# SCH_ch559_2022-01-07.net
KiCad netlist of a schematic drawn in EasyEDA
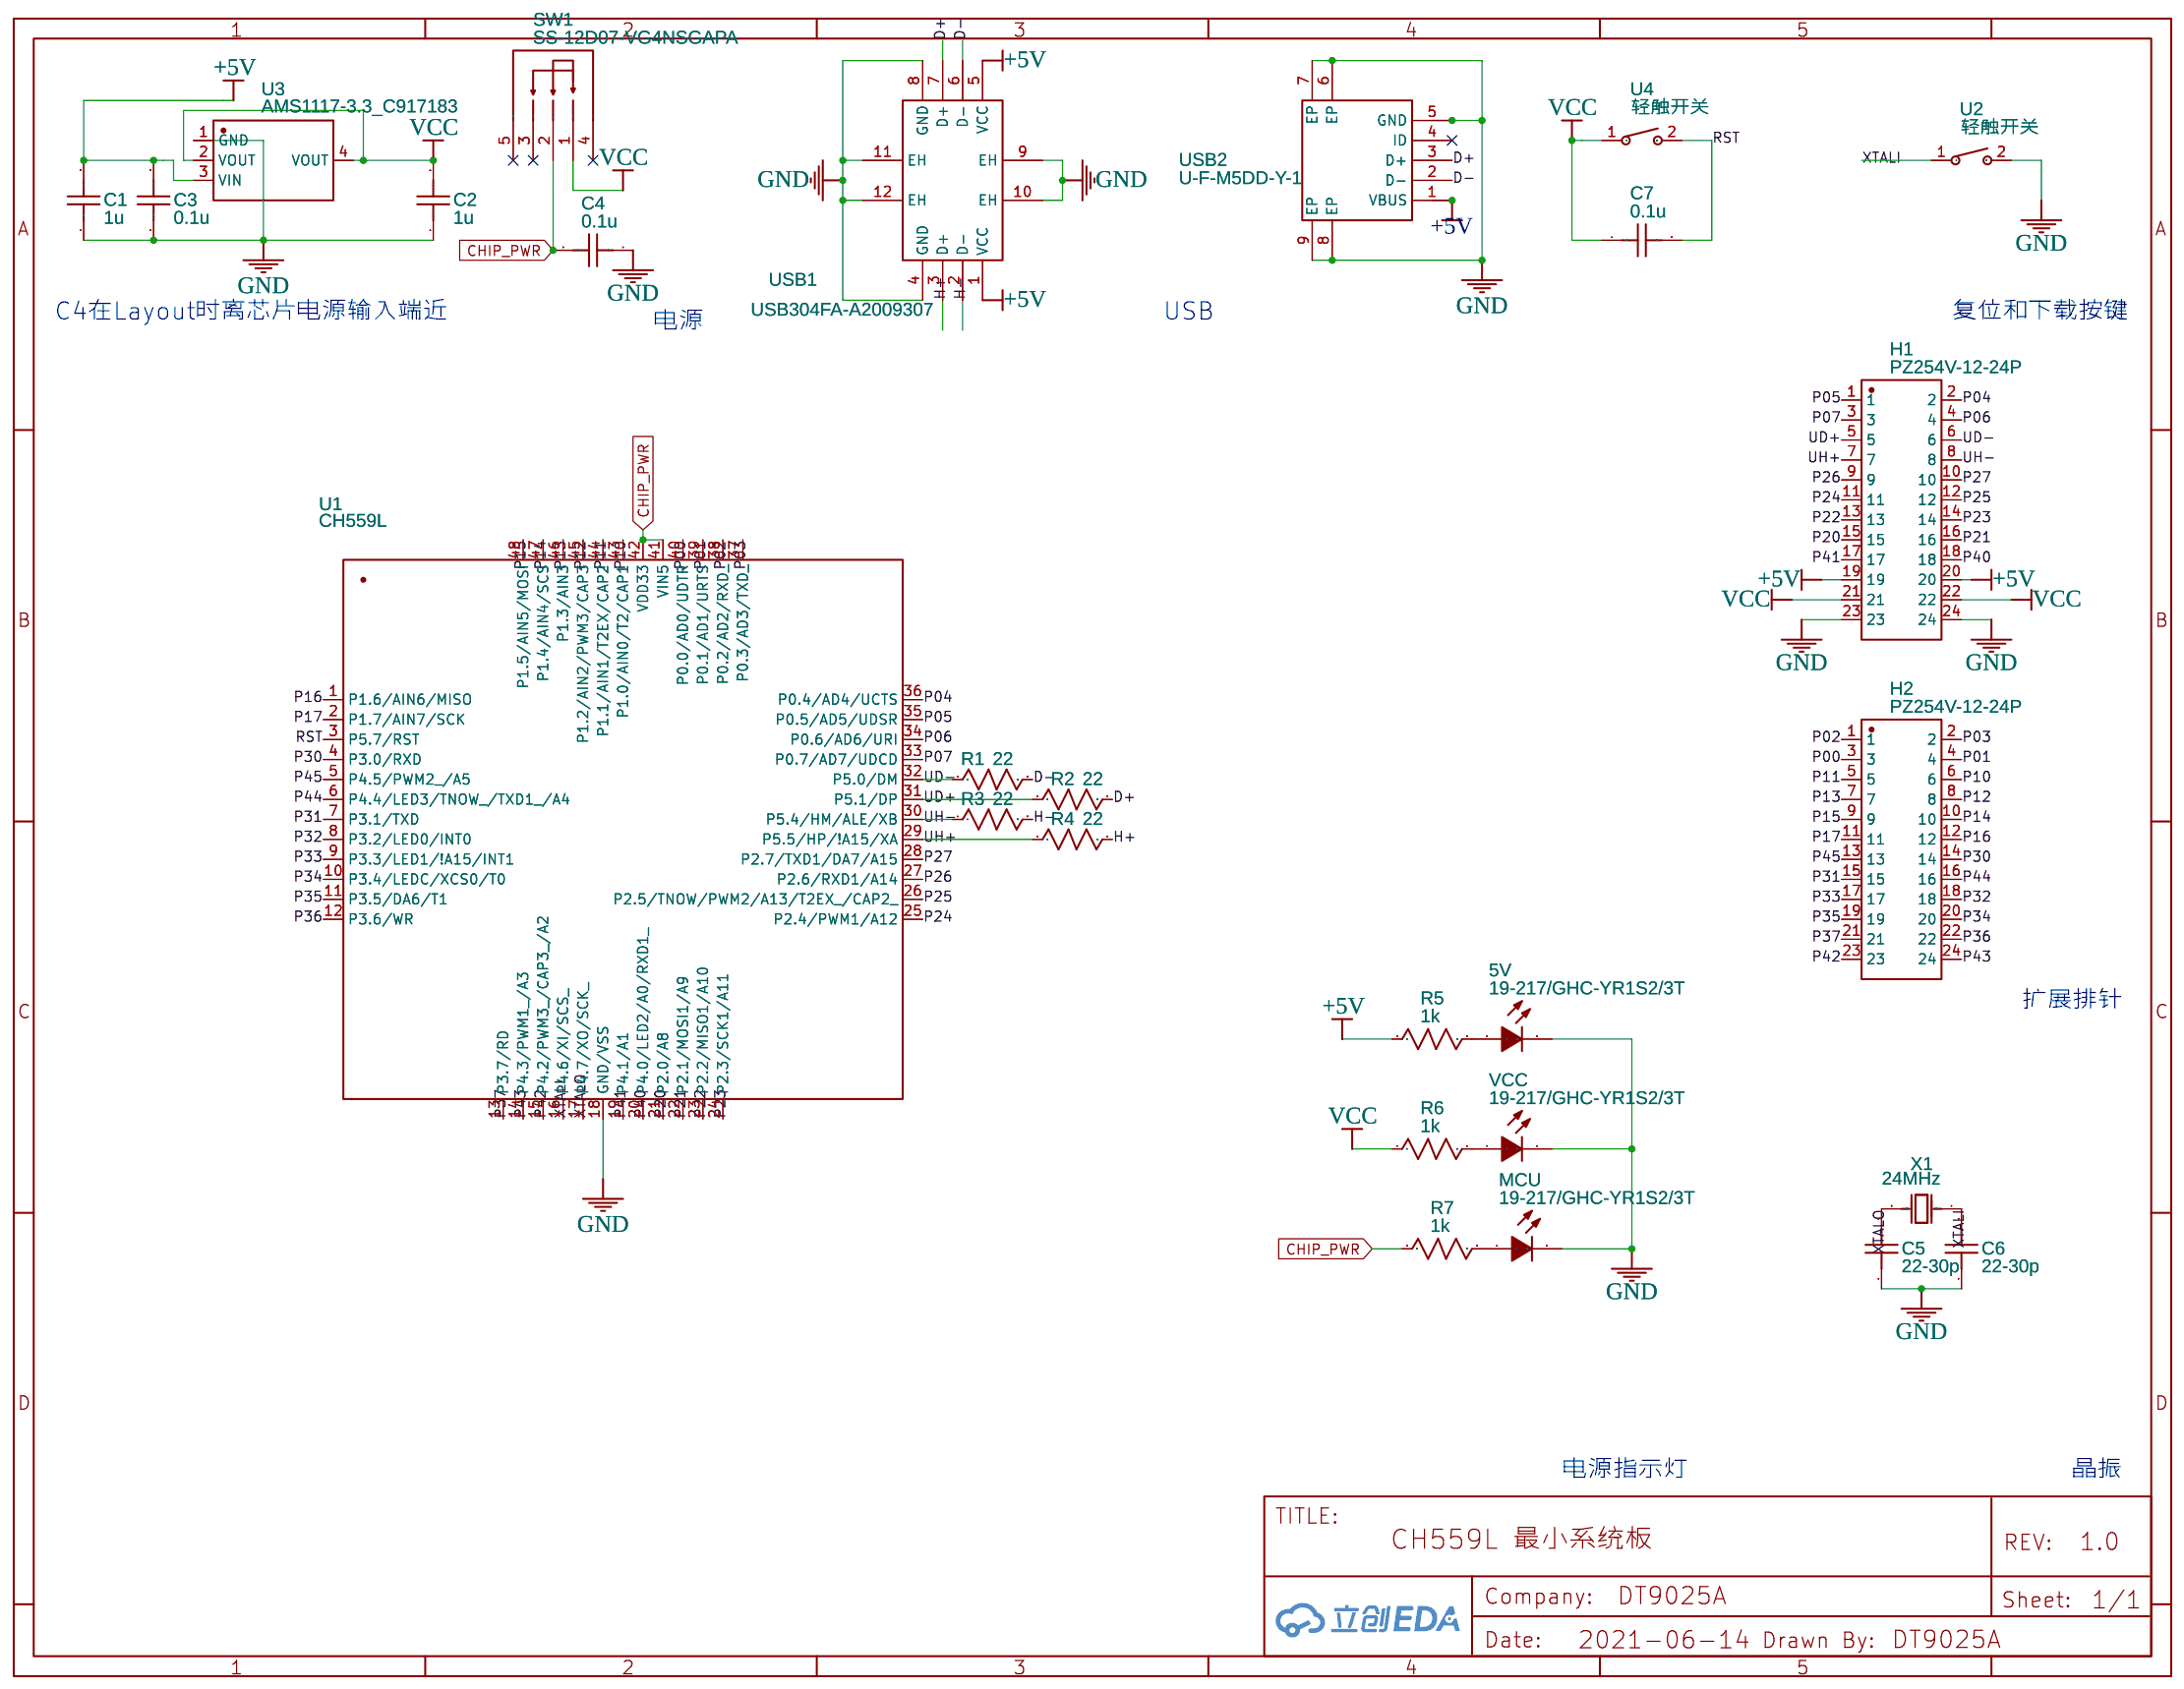
[diagram p0: schematic sheet]

(export (version "E")
  (design (tool "Eeschema 10.0.6"))
  (components
    (comp (ref "5V")
      (value "19-217/GHC-YR1S2/3T")
      (fields (field (name "BOM_Supplier Part") "C72043"))
      (libsource (lib "") (part "19-217/GHC-YR1S2/3T"))
    )
    (comp (ref "C1") (value "1u") (libsource (lib "") (part "C_0603_US")))
    (comp (ref "C2") (value "1u") (libsource (lib "") (part "C_0603_US")))
    (comp (ref "C3") (value "0.1u") (libsource (lib "") (part "C_0805_US")))
    (comp (ref "C4") (value "0.1u") (libsource (lib "") (part "C_0805_US_1")))
    (comp (ref "C5") (value "22-30p") (libsource (lib "") (part "C_0805_US")))
    (comp (ref "C6") (value "22-30p") (libsource (lib "") (part "C_0805_US")))
    (comp (ref "C7") (value "0.1u") (libsource (lib "") (part "C_0805_US_2")))
    (comp (ref "H1")
      (value "PZ254V-12-24P")
      (fields (field (name "BOM_Supplier Part") "C492429"))
      (libsource (lib "") (part "PZ254V-12-24P"))
    )
    (comp (ref "H2")
      (value "PZ254V-12-24P")
      (fields (field (name "BOM_Supplier Part") "C492429"))
      (libsource (lib "") (part "PZ254V-12-24P"))
    )
    (comp (ref "MCU")
      (value "19-217/GHC-YR1S2/3T")
      (fields (field (name "BOM_Supplier Part") "C72043"))
      (libsource (lib "") (part "19-217/GHC-YR1S2/3T_2"))
    )
    (comp (ref "R1") (value "22") (libsource (lib "") (part "R_0603_US")))
    (comp (ref "R2") (value "22") (libsource (lib "") (part "R_0603_US")))
    (comp (ref "R3") (value "22") (libsource (lib "") (part "R_0603_US")))
    (comp (ref "R4") (value "22") (libsource (lib "") (part "R_0603_US")))
    (comp (ref "R5") (value "1k") (libsource (lib "") (part "R_0603_US")))
    (comp (ref "R6") (value "1k") (libsource (lib "") (part "R_0603_US")))
    (comp (ref "R7") (value "1k") (libsource (lib "") (part "R_0603_US")))
    (comp (ref "SW1")
      (value "SS-12D07-VG4NSGAPA")
      (fields (field (name "BOM_Supplier Part") "C221975"))
      (libsource (lib "") (part "SS-12D07-VG4NSGAPA"))
    )
    (comp (ref "U1")
      (value "CH559L")
      (fields (field (name "BOM_Supplier Part") "C150548"))
      (libsource (lib "") (part "CH559L"))
    )
    (comp (ref "U2")
      (value "轻触开关")
      (fields (field (name "BOM_Supplier Part") "C9900000012"))
      (libsource (lib "") (part "轻触开关"))
    )
    (comp (ref "U3")
      (value "AMS1117-3.3_C917183")
      (fields
        (field (name "BOM_Manufacturer Part") "AMS1117-3.3")
        (field (name "BOM_Supplier Part") "C917183")
      )
      (libsource (lib "") (part "AMS1117-3.3_C917183"))
    )
    (comp (ref "U4")
      (value "轻触开关")
      (fields (field (name "BOM_Supplier Part") "C9900000012"))
      (libsource (lib "") (part "轻触开关"))
    )
    (comp (ref "USB1")
      (value "USB304FA-A2009307")
      (fields (field (name "BOM_Supplier Part") "C479985"))
      (libsource (lib "") (part "USB304FA-A2009307"))
    )
    (comp (ref "USB2")
      (value "U-F-M5DD-Y-1")
      (fields (field (name "BOM_Supplier Part") "C91467"))
      (libsource (lib "") (part "U-F-M5DD-Y-1"))
    )
    (comp (ref "VCC")
      (value "19-217/GHC-YR1S2/3T")
      (fields (field (name "BOM_Supplier Part") "C72043"))
      (libsource (lib "") (part "19-217/GHC-YR1S2/3T_1"))
    )
    (comp (ref "X1")
      (value "24MHz")
      (fields
        (field (name "BOM_Manufacturer Part") "X49SD24MSD2SC")
        (field (name "BOM_Supplier Part") "C2213")
      )
      (libsource (lib "") (part "X49SD24MSD2SC"))
    )
  )
  (nets
    (net (code "1") (name "+5V") (class "Default")
      (node (ref "C1") (pin "2") (pinfunction "2_2") (pintype "unspecified"))
      (node (ref "C3") (pin "2") (pinfunction "2_2") (pintype "unspecified"))
      (node (ref "H1") (pin "19") (pinfunction "19_19") (pintype "unspecified"))
      (node (ref "H1") (pin "20") (pinfunction "20_20") (pintype "unspecified"))
      (node (ref "R5") (pin "1") (pinfunction "1_1") (pintype "unspecified"))
      (node (ref "U3") (pin "3") (pinfunction "VIN_3") (pintype "unspecified"))
      (node (ref "USB1") (pin "1") (pinfunction "VCC_1") (pintype "unspecified"))
      (node (ref "USB1") (pin "5") (pinfunction "VCC_5") (pintype "unspecified"))
      (node (ref "USB2") (pin "1") (pinfunction "VBUS_1") (pintype "unspecified"))
    )
    (net (code "2") (name "/D+") (class "Default")
      (node (ref "R2") (pin "2") (pinfunction "2_2") (pintype "unspecified"))
      (node (ref "USB1") (pin "7") (pinfunction "D+_7") (pintype "unspecified"))
      (node (ref "USB2") (pin "3") (pinfunction "D+_3") (pintype "unspecified"))
    )
    (net (code "3") (name "/D-") (class "Default")
      (node (ref "R1") (pin "2") (pinfunction "2_2") (pintype "unspecified"))
      (node (ref "USB1") (pin "6") (pinfunction "D-_6") (pintype "unspecified"))
      (node (ref "USB2") (pin "2") (pinfunction "D-_2") (pintype "unspecified"))
    )
    (net (code "4") (name "/H+") (class "Default")
      (node (ref "R4") (pin "2") (pinfunction "2_2") (pintype "unspecified"))
      (node (ref "USB1") (pin "3") (pinfunction "D+_3") (pintype "unspecified"))
    )
    (net (code "5") (name "/H-") (class "Default")
      (node (ref "R3") (pin "2") (pinfunction "2_2") (pintype "unspecified"))
      (node (ref "USB1") (pin "2") (pinfunction "D-_2") (pintype "unspecified"))
    )
    (net (code "6") (name "/P00") (class "Default")
      (node (ref "H2") (pin "3") (pinfunction "3_3") (pintype "unspecified"))
      (node (ref "U1") (pin "40") (pinfunction "P0.0/AD0/UDTR_40") (pintype "unspecified"))
    )
    (net (code "7") (name "/P01") (class "Default")
      (node (ref "H2") (pin "4") (pinfunction "4_4") (pintype "unspecified"))
      (node (ref "U1") (pin "39") (pinfunction "P0.1/AD1/URTS_39") (pintype "unspecified"))
    )
    (net (code "8") (name "/P02") (class "Default")
      (node (ref "H2") (pin "1") (pinfunction "1_1") (pintype "unspecified"))
      (node (ref "U1") (pin "38") (pinfunction "P0.2/AD2/RXD__38") (pintype "unspecified"))
    )
    (net (code "9") (name "/P03") (class "Default")
      (node (ref "H2") (pin "2") (pinfunction "2_2") (pintype "unspecified"))
      (node (ref "U1") (pin "37") (pinfunction "P0.3/AD3/TXD__37") (pintype "unspecified"))
    )
    (net (code "10") (name "/P04") (class "Default")
      (node (ref "H1") (pin "2") (pinfunction "2_2") (pintype "unspecified"))
      (node (ref "U1") (pin "36") (pinfunction "P0.4/AD4/UCTS_36") (pintype "unspecified"))
    )
    (net (code "11") (name "/P05") (class "Default")
      (node (ref "H1") (pin "1") (pinfunction "1_1") (pintype "unspecified"))
      (node (ref "U1") (pin "35") (pinfunction "P0.5/AD5/UDSR_35") (pintype "unspecified"))
    )
    (net (code "12") (name "/P06") (class "Default")
      (node (ref "H1") (pin "4") (pinfunction "4_4") (pintype "unspecified"))
      (node (ref "U1") (pin "34") (pinfunction "P0.6/AD6/URI_34") (pintype "unspecified"))
    )
    (net (code "13") (name "/P07") (class "Default")
      (node (ref "H1") (pin "3") (pinfunction "3_3") (pintype "unspecified"))
      (node (ref "U1") (pin "33") (pinfunction "P0.7/AD7/UDCD_33") (pintype "unspecified"))
    )
    (net (code "14") (name "/P10") (class "Default")
      (node (ref "H2") (pin "6") (pinfunction "6_6") (pintype "unspecified"))
      (node (ref "U1") (pin "43") (pinfunction "P1.0/AIN0/T2/CAP1_43") (pintype "unspecified"))
    )
    (net (code "15") (name "/P11") (class "Default")
      (node (ref "H2") (pin "5") (pinfunction "5_5") (pintype "unspecified"))
      (node (ref "U1") (pin "44") (pinfunction "P1.1/AIN1/T2EX/CAP2_44") (pintype "unspecified"))
    )
    (net (code "16") (name "/P12") (class "Default")
      (node (ref "H2") (pin "8") (pinfunction "8_8") (pintype "unspecified"))
      (node (ref "U1") (pin "45") (pinfunction "P1.2/AIN2/PWM3/CAP3_45") (pintype "unspecified"))
    )
    (net (code "17") (name "/P13") (class "Default")
      (node (ref "H2") (pin "7") (pinfunction "7_7") (pintype "unspecified"))
      (node (ref "U1") (pin "46") (pinfunction "P1.3/AIN3_46") (pintype "unspecified"))
    )
    (net (code "18") (name "/P14") (class "Default")
      (node (ref "H2") (pin "10") (pinfunction "10_10") (pintype "unspecified"))
      (node (ref "U1") (pin "47") (pinfunction "P1.4/AIN4/SCS_47") (pintype "unspecified"))
    )
    (net (code "19") (name "/P15") (class "Default")
      (node (ref "H2") (pin "9") (pinfunction "9_9") (pintype "unspecified"))
      (node (ref "U1") (pin "48") (pinfunction "P1.5/AIN5/MOSI_48") (pintype "unspecified"))
    )
    (net (code "20") (name "/P16") (class "Default")
      (node (ref "H2") (pin "12") (pinfunction "12_12") (pintype "unspecified"))
      (node (ref "U1") (pin "1") (pinfunction "P1.6/AIN6/MISO_1") (pintype "unspecified"))
    )
    (net (code "21") (name "/P17") (class "Default")
      (node (ref "H2") (pin "11") (pinfunction "11_11") (pintype "unspecified"))
      (node (ref "U1") (pin "2") (pinfunction "P1.7/AIN7/SCK_2") (pintype "unspecified"))
    )
    (net (code "22") (name "/P20") (class "Default")
      (node (ref "H1") (pin "15") (pinfunction "15_15") (pintype "unspecified"))
      (node (ref "U1") (pin "21") (pinfunction "P2.0/A8_21") (pintype "unspecified"))
    )
    (net (code "23") (name "/P21") (class "Default")
      (node (ref "H1") (pin "16") (pinfunction "16_16") (pintype "unspecified"))
      (node (ref "U1") (pin "22") (pinfunction "P2.1/MOSI1/A9_22") (pintype "unspecified"))
    )
    (net (code "24") (name "/P22") (class "Default")
      (node (ref "H1") (pin "13") (pinfunction "13_13") (pintype "unspecified"))
      (node (ref "U1") (pin "23") (pinfunction "P2.2/MISO1/A10_23") (pintype "unspecified"))
    )
    (net (code "25") (name "/P23") (class "Default")
      (node (ref "H1") (pin "14") (pinfunction "14_14") (pintype "unspecified"))
      (node (ref "U1") (pin "24") (pinfunction "P2.3/SCK1/A11_24") (pintype "unspecified"))
    )
    (net (code "26") (name "/P24") (class "Default")
      (node (ref "H1") (pin "11") (pinfunction "11_11") (pintype "unspecified"))
      (node (ref "U1") (pin "25") (pinfunction "P2.4/PWM1/A12_25") (pintype "unspecified"))
    )
    (net (code "27") (name "/P25") (class "Default")
      (node (ref "H1") (pin "12") (pinfunction "12_12") (pintype "unspecified"))
      (node (ref "U1") (pin "26") (pinfunction "P2.5/TNOW/PWM2/A13/T2EX_/CAP2__26") (pintype "unspecified"))
    )
    (net (code "28") (name "/P26") (class "Default")
      (node (ref "H1") (pin "9") (pinfunction "9_9") (pintype "unspecified"))
      (node (ref "U1") (pin "27") (pinfunction "P2.6/RXD1/A14_27") (pintype "unspecified"))
    )
    (net (code "29") (name "/P27") (class "Default")
      (node (ref "H1") (pin "10") (pinfunction "10_10") (pintype "unspecified"))
      (node (ref "U1") (pin "28") (pinfunction "P2.7/TXD1/DA7/A15_28") (pintype "unspecified"))
    )
    (net (code "30") (name "/P30") (class "Default")
      (node (ref "H2") (pin "14") (pinfunction "14_14") (pintype "unspecified"))
      (node (ref "U1") (pin "4") (pinfunction "P3.0/RXD_4") (pintype "unspecified"))
    )
    (net (code "31") (name "/P31") (class "Default")
      (node (ref "H2") (pin "15") (pinfunction "15_15") (pintype "unspecified"))
      (node (ref "U1") (pin "7") (pinfunction "P3.1/TXD_7") (pintype "unspecified"))
    )
    (net (code "32") (name "/P32") (class "Default")
      (node (ref "H2") (pin "18") (pinfunction "18_18") (pintype "unspecified"))
      (node (ref "U1") (pin "8") (pinfunction "P3.2/LED0/INT0_8") (pintype "unspecified"))
    )
    (net (code "33") (name "/P33") (class "Default")
      (node (ref "H2") (pin "17") (pinfunction "17_17") (pintype "unspecified"))
      (node (ref "U1") (pin "9") (pinfunction "P3.3/LED1/!A15/INT1_9") (pintype "unspecified"))
    )
    (net (code "34") (name "/P34") (class "Default")
      (node (ref "H2") (pin "20") (pinfunction "20_20") (pintype "unspecified"))
      (node (ref "U1") (pin "10") (pinfunction "P3.4/LEDC/XCS0/T0_10") (pintype "unspecified"))
    )
    (net (code "35") (name "/P35") (class "Default")
      (node (ref "H2") (pin "19") (pinfunction "19_19") (pintype "unspecified"))
      (node (ref "U1") (pin "11") (pinfunction "P3.5/DA6/T1_11") (pintype "unspecified"))
    )
    (net (code "36") (name "/P36") (class "Default")
      (node (ref "H2") (pin "22") (pinfunction "22_22") (pintype "unspecified"))
      (node (ref "U1") (pin "12") (pinfunction "P3.6/WR_12") (pintype "unspecified"))
    )
    (net (code "37") (name "/P37") (class "Default")
      (node (ref "H2") (pin "21") (pinfunction "21_21") (pintype "unspecified"))
      (node (ref "U1") (pin "13") (pinfunction "P3.7/RD_13") (pintype "unspecified"))
    )
    (net (code "38") (name "/P40") (class "Default")
      (node (ref "H1") (pin "18") (pinfunction "18_18") (pintype "unspecified"))
      (node (ref "U1") (pin "20") (pinfunction "P4.0/LED2/A0/RXD1__20") (pintype "unspecified"))
    )
    (net (code "39") (name "/P41") (class "Default")
      (node (ref "H1") (pin "17") (pinfunction "17_17") (pintype "unspecified"))
      (node (ref "U1") (pin "19") (pinfunction "P4.1/A1_19") (pintype "unspecified"))
    )
    (net (code "40") (name "/P42") (class "Default")
      (node (ref "H2") (pin "23") (pinfunction "23_23") (pintype "unspecified"))
      (node (ref "U1") (pin "15") (pinfunction "P4.2/PWM3_/CAP3_/A2_15") (pintype "unspecified"))
    )
    (net (code "41") (name "/P43") (class "Default")
      (node (ref "H2") (pin "24") (pinfunction "24_24") (pintype "unspecified"))
      (node (ref "U1") (pin "14") (pinfunction "P4.3/PWM1_/A3_14") (pintype "unspecified"))
    )
    (net (code "42") (name "/P44") (class "Default")
      (node (ref "H2") (pin "16") (pinfunction "16_16") (pintype "unspecified"))
      (node (ref "U1") (pin "6") (pinfunction "P4.4/LED3/TNOW_/TXD1_/A4_6") (pintype "unspecified"))
    )
    (net (code "43") (name "/P45") (class "Default")
      (node (ref "H2") (pin "13") (pinfunction "13_13") (pintype "unspecified"))
      (node (ref "U1") (pin "5") (pinfunction "P4.5/PWM2_/A5_5") (pintype "unspecified"))
    )
    (net (code "44") (name "/RST") (class "Default")
      (node (ref "C7") (pin "2") (pinfunction "2_2") (pintype "unspecified"))
      (node (ref "U1") (pin "3") (pinfunction "P5.7/RST_3") (pintype "unspecified"))
      (node (ref "U4") (pin "2") (pinfunction "2_2") (pintype "unspecified"))
    )
    (net (code "45") (name "/UD+") (class "Default")
      (node (ref "H1") (pin "5") (pinfunction "5_5") (pintype "unspecified"))
      (node (ref "R2") (pin "1") (pinfunction "1_1") (pintype "unspecified"))
      (node (ref "U1") (pin "31") (pinfunction "P5.1/DP_31") (pintype "unspecified"))
    )
    (net (code "46") (name "/UD-") (class "Default")
      (node (ref "H1") (pin "6") (pinfunction "6_6") (pintype "unspecified"))
      (node (ref "R1") (pin "1") (pinfunction "1_1") (pintype "unspecified"))
      (node (ref "U1") (pin "32") (pinfunction "P5.0/DM_32") (pintype "unspecified"))
    )
    (net (code "47") (name "/UH+") (class "Default")
      (node (ref "H1") (pin "7") (pinfunction "7_7") (pintype "unspecified"))
      (node (ref "R4") (pin "1") (pinfunction "1_1") (pintype "unspecified"))
      (node (ref "U1") (pin "29") (pinfunction "P5.5/HP/!A15/XA_29") (pintype "unspecified"))
    )
    (net (code "48") (name "/UH-") (class "Default")
      (node (ref "H1") (pin "8") (pinfunction "8_8") (pintype "unspecified"))
      (node (ref "R3") (pin "1") (pinfunction "1_1") (pintype "unspecified"))
      (node (ref "U1") (pin "30") (pinfunction "P5.4/HM/ALE/XB_30") (pintype "unspecified"))
    )
    (net (code "49") (name "/XTALI") (class "Default")
      (node (ref "C6") (pin "2") (pinfunction "2_2") (pintype "unspecified"))
      (node (ref "U1") (pin "16") (pinfunction "P4.6/XI/SCS__16") (pintype "unspecified"))
      (node (ref "U2") (pin "1") (pinfunction "1_1") (pintype "unspecified"))
      (node (ref "X1") (pin "1") (pinfunction "OSC1_1") (pintype "input"))
    )
    (net (code "50") (name "/XTALO") (class "Default")
      (node (ref "C5") (pin "2") (pinfunction "2_2") (pintype "unspecified"))
      (node (ref "U1") (pin "17") (pinfunction "P4.7/XO/SCK__17") (pintype "unspecified"))
      (node (ref "X1") (pin "2") (pinfunction "OSC2_2") (pintype "input"))
    )
    (net (code "51") (name "CHIP_PWR") (class "Default")
      (node (ref "C4") (pin "2") (pinfunction "2_2") (pintype "unspecified"))
      (node (ref "R7") (pin "1") (pinfunction "1_1") (pintype "unspecified"))
      (node (ref "SW1") (pin "2") (pinfunction "2_2") (pintype "unspecified"))
      (node (ref "U1") (pin "41") (pinfunction "VIN5_41") (pintype "unspecified"))
      (node (ref "U1") (pin "42") (pinfunction "VDD33_42") (pintype "unspecified"))
    )
    (net (code "52") (name "GND") (class "Default")
      (node (ref "5V") (pin "2") (pinfunction "C_2") (pintype "input"))
      (node (ref "C1") (pin "1") (pinfunction "1_1") (pintype "unspecified"))
      (node (ref "C2") (pin "1") (pinfunction "1_1") (pintype "unspecified"))
      (node (ref "C3") (pin "1") (pinfunction "1_1") (pintype "unspecified"))
      (node (ref "C4") (pin "1") (pinfunction "1_1") (pintype "unspecified"))
      (node (ref "C5") (pin "1") (pinfunction "1_1") (pintype "unspecified"))
      (node (ref "C6") (pin "1") (pinfunction "1_1") (pintype "unspecified"))
      (node (ref "H1") (pin "23") (pinfunction "23_23") (pintype "unspecified"))
      (node (ref "H1") (pin "24") (pinfunction "24_24") (pintype "unspecified"))
      (node (ref "MCU") (pin "2") (pinfunction "C_2") (pintype "input"))
      (node (ref "U1") (pin "18") (pinfunction "GND/VSS_18") (pintype "unspecified"))
      (node (ref "U2") (pin "2") (pinfunction "2_2") (pintype "unspecified"))
      (node (ref "U3") (pin "1") (pinfunction "GND_1") (pintype "unspecified"))
      (node (ref "USB1") (pin "10") (pinfunction "EH_10") (pintype "unspecified"))
      (node (ref "USB1") (pin "11") (pinfunction "EH_11") (pintype "unspecified"))
      (node (ref "USB1") (pin "12") (pinfunction "EH_12") (pintype "unspecified"))
      (node (ref "USB1") (pin "4") (pinfunction "GND_4") (pintype "unspecified"))
      (node (ref "USB1") (pin "8") (pinfunction "GND_8") (pintype "unspecified"))
      (node (ref "USB1") (pin "9") (pinfunction "EH_9") (pintype "unspecified"))
      (node (ref "USB2") (pin "5") (pinfunction "GND_5") (pintype "unspecified"))
      (node (ref "USB2") (pin "6") (pinfunction "EP_6") (pintype "unspecified"))
      (node (ref "USB2") (pin "7") (pinfunction "EP_7") (pintype "unspecified"))
      (node (ref "USB2") (pin "8") (pinfunction "EP_8") (pintype "unspecified"))
      (node (ref "USB2") (pin "9") (pinfunction "EP_9") (pintype "unspecified"))
      (node (ref "VCC") (pin "2") (pinfunction "C_2") (pintype "input"))
    )
    (net (code "53") (name "Net-(5V-A)") (class "Default")
      (node (ref "5V") (pin "1") (pinfunction "A_1") (pintype "input"))
      (node (ref "R5") (pin "2") (pinfunction "2_2") (pintype "unspecified"))
    )
    (net (code "54") (name "Net-(MCU-A)") (class "Default")
      (node (ref "MCU") (pin "1") (pinfunction "A_1") (pintype "input"))
      (node (ref "R7") (pin "2") (pinfunction "2_2") (pintype "unspecified"))
    )
    (net (code "55") (name "Net-(VCC-A)") (class "Default")
      (node (ref "R6") (pin "2") (pinfunction "2_2") (pintype "unspecified"))
      (node (ref "VCC") (pin "1") (pinfunction "A_1") (pintype "input"))
    )
    (net (code "56") (name "VCC") (class "Default")
      (node (ref "C2") (pin "2") (pinfunction "2_2") (pintype "unspecified"))
      (node (ref "C7") (pin "1") (pinfunction "1_1") (pintype "unspecified"))
      (node (ref "H1") (pin "21") (pinfunction "21_21") (pintype "unspecified"))
      (node (ref "H1") (pin "22") (pinfunction "22_22") (pintype "unspecified"))
      (node (ref "R6") (pin "1") (pinfunction "1_1") (pintype "unspecified"))
      (node (ref "SW1") (pin "1") (pinfunction "1_1") (pintype "unspecified"))
      (node (ref "U3") (pin "2") (pinfunction "VOUT_2") (pintype "unspecified"))
      (node (ref "U3") (pin "4") (pinfunction "VOUT_4") (pintype "unspecified"))
      (node (ref "U4") (pin "1") (pinfunction "1_1") (pintype "unspecified"))
    )
    (net (code "57") (name "unconnected-(SW1-Pad3)") (class "Default")
      (node (ref "SW1") (pin "3") (pinfunction "3_3") (pintype "unspecified+no_connect"))
    )
    (net (code "58") (name "unconnected-(SW1-Pad4)") (class "Default")
      (node (ref "SW1") (pin "4") (pinfunction "4_4") (pintype "unspecified+no_connect"))
    )
    (net (code "59") (name "unconnected-(SW1-Pad5)") (class "Default")
      (node (ref "SW1") (pin "5") (pinfunction "5_5") (pintype "unspecified+no_connect"))
    )
    (net (code "60") (name "unconnected-(USB2-ID-Pad4)") (class "Default")
      (node (ref "USB2") (pin "4") (pinfunction "ID_4") (pintype "unspecified+no_connect"))
    )
  )
)
